# schemetics.net
KiCad netlist of a schematic drawn in EasyEDA
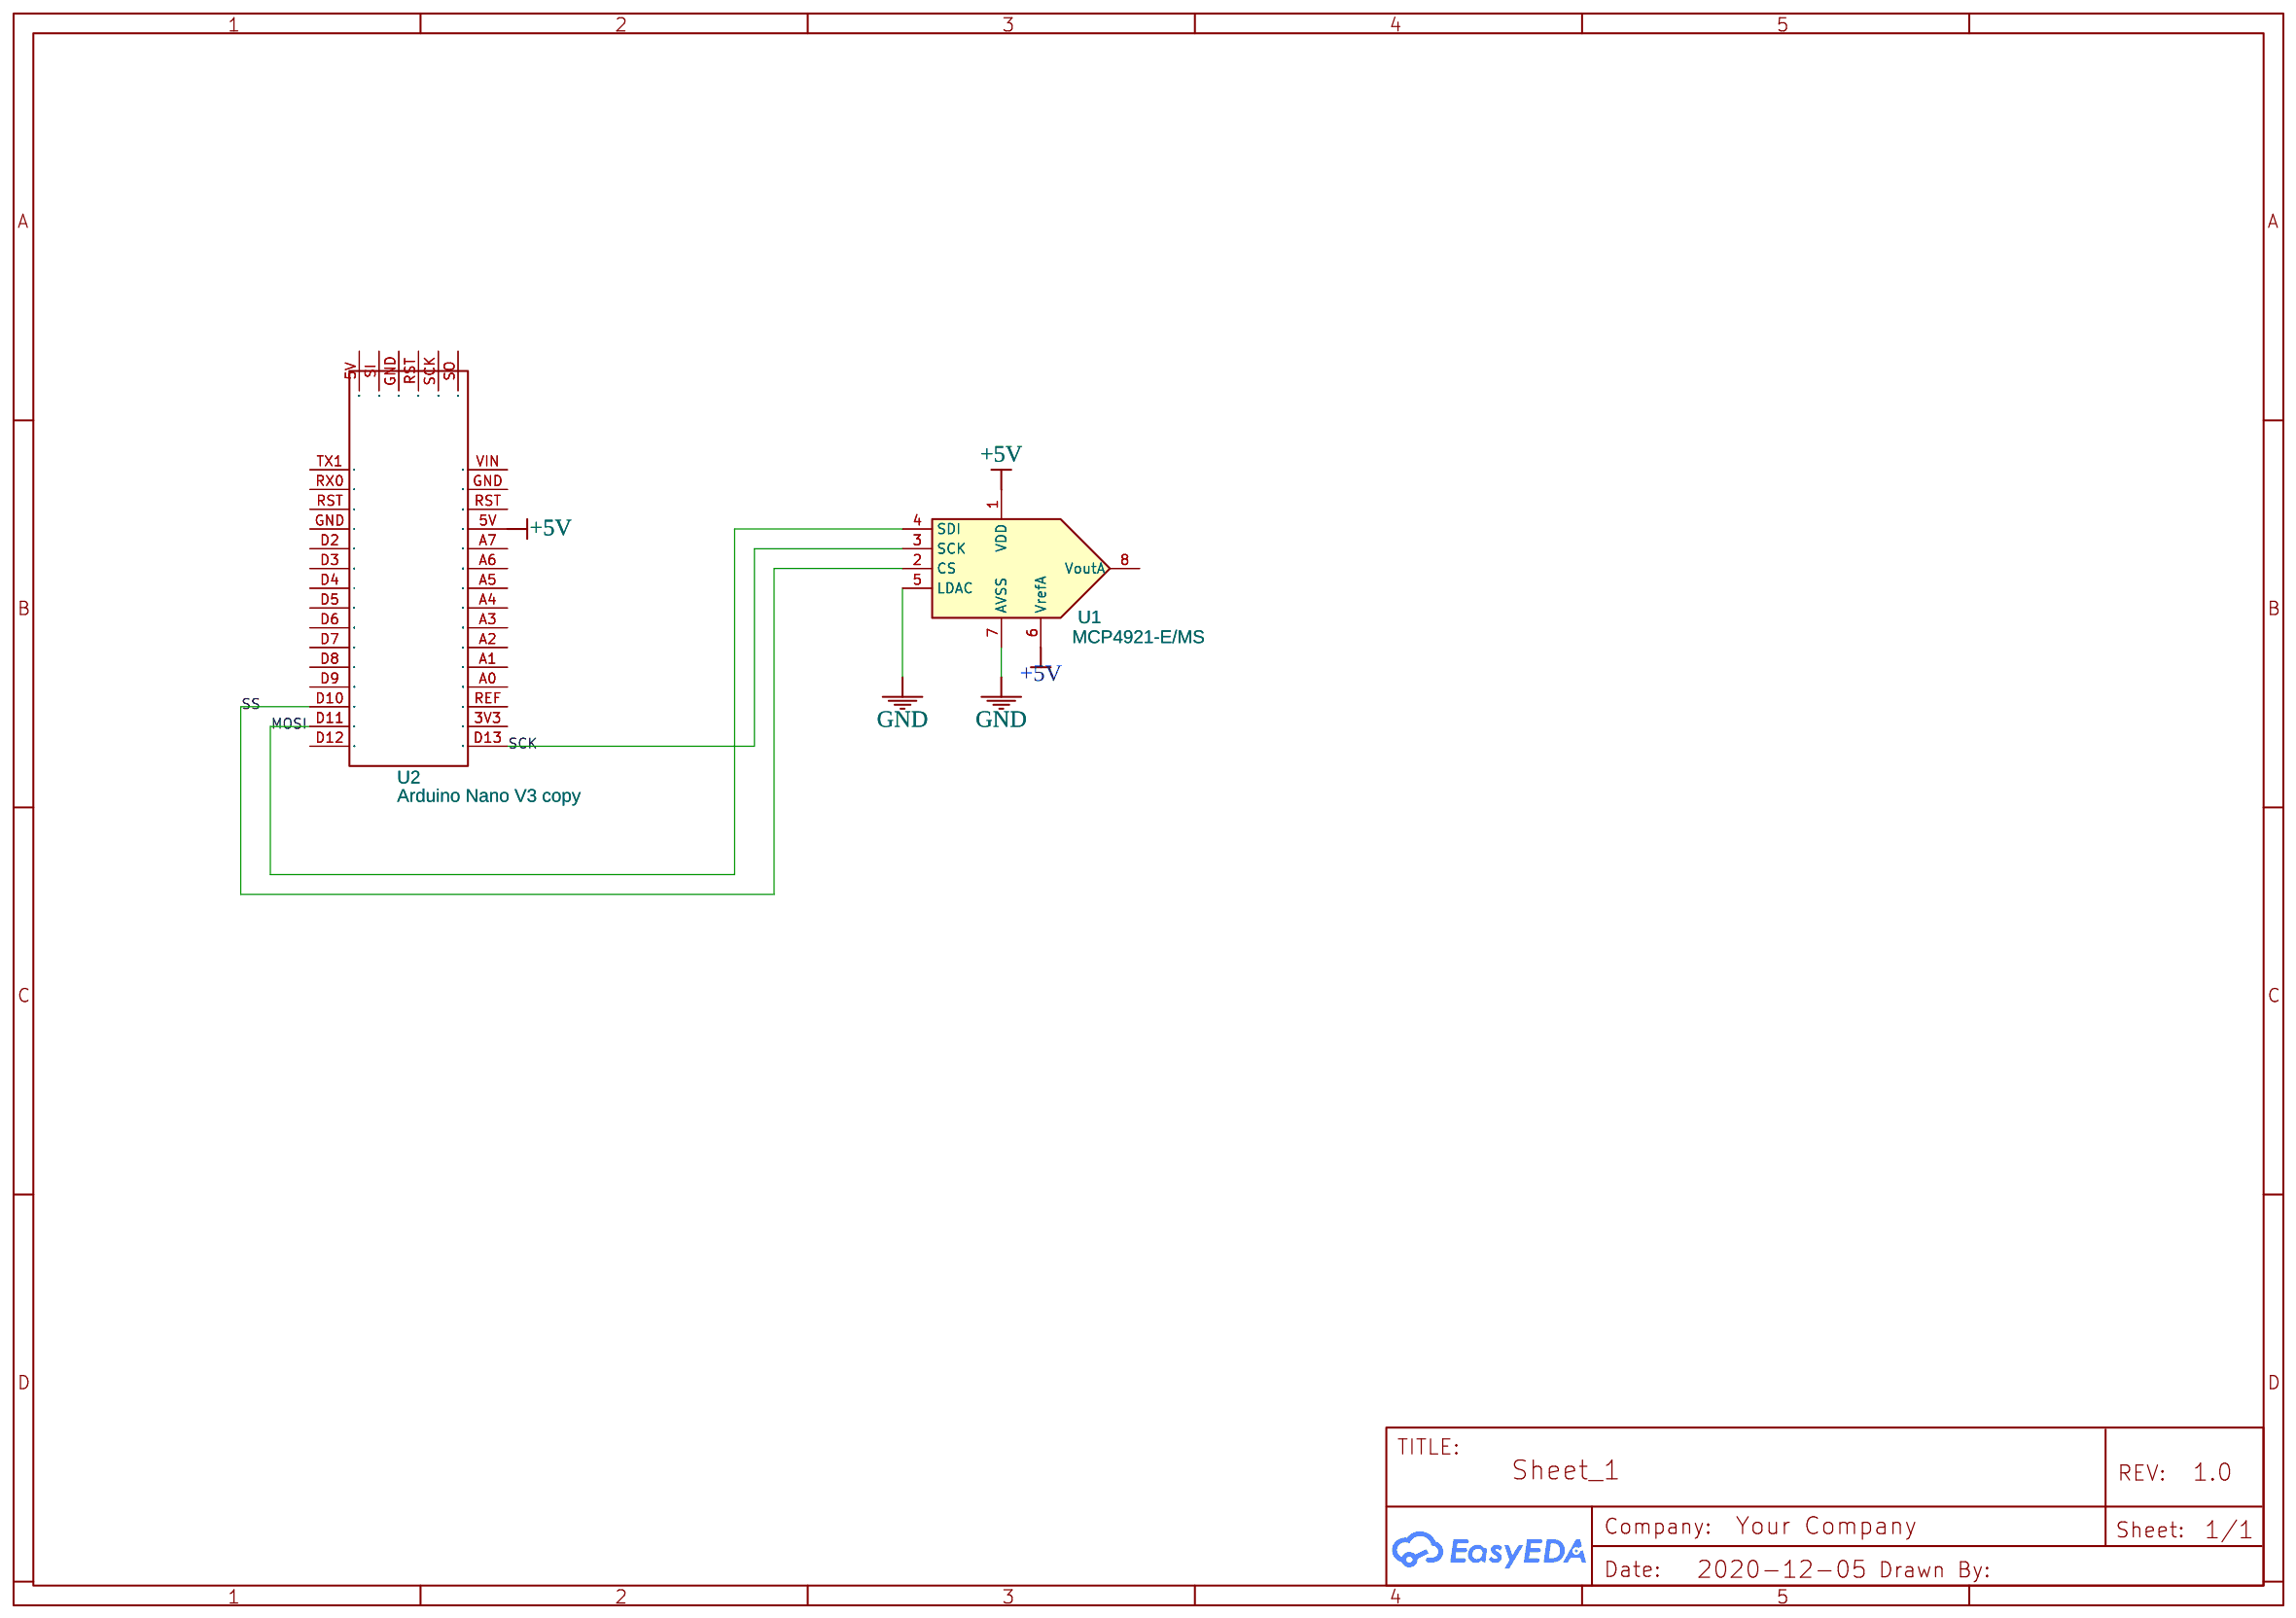
[diagram p0: schematic sheet]

(export (version "E")
  (design (tool "Eeschema 10.0.6"))
  (components
    (comp (ref "U1") (value "MCP4921-E/MS") (libsource (lib "") (part "MCP4921-E/MS")))
    (comp (ref "U2")
      (value "Arduino Nano V3 copy")
      (fields (field (name "BOM_Manufacturer Part") "Arduino Nano V3"))
      (libsource (lib "") (part "Arduino Nano V3 copy"))
    )
  )
  (nets
    (net (code "1") (name "+5V") (class "Default")
      (node (ref "U1") (pin "1") (pinfunction "VDD_1") (pintype "bidirectional"))
      (node (ref "U1") (pin "6") (pinfunction "VrefA_6") (pintype "unspecified"))
      (node (ref "U2") (pin "5V") (pinfunction "27_5V") (pintype "unspecified"))
    )
    (net (code "2") (name "/MOSI") (class "Default")
      (node (ref "U1") (pin "4") (pinfunction "SDI_4") (pintype "input"))
      (node (ref "U2") (pin "D11") (pinfunction "14_D11") (pintype "unspecified"))
    )
    (net (code "3") (name "/SCK") (class "Default")
      (node (ref "U1") (pin "3") (pinfunction "SCK_3") (pintype "input"))
      (node (ref "U2") (pin "D13") (pinfunction "16_D13") (pintype "unspecified"))
    )
    (net (code "4") (name "/SS") (class "Default")
      (node (ref "U1") (pin "2") (pinfunction "CS_2") (pintype "input"))
      (node (ref "U2") (pin "D10") (pinfunction "13_D10") (pintype "unspecified"))
    )
    (net (code "5") (name "GND") (class "Default")
      (node (ref "U1") (pin "5") (pinfunction "LDAC_5") (pintype "input"))
      (node (ref "U1") (pin "7") (pinfunction "AVSS_7") (pintype "bidirectional"))
    )
    (net (code "6") (name "unconnected-(U1-VoutA-Pad8)") (class "Default")
      (node (ref "U1") (pin "8") (pinfunction "VoutA_8") (pintype "unspecified"))
    )
    (net (code "7") (name "unconnected-(U2-1-PadTX1)") (class "Default")
      (node (ref "U2") (pin "TX1") (pinfunction "1_TX1") (pintype "unspecified"))
    )
    (net (code "8") (name "unconnected-(U2-2-PadRX0)") (class "Default")
      (node (ref "U2") (pin "RX0") (pinfunction "2_RX0") (pintype "unspecified"))
    )
    (net (code "9") (name "unconnected-(U2-3-PadRST)") (class "Default")
      (node (ref "U2") (pin "RST") (pinfunction "3_RST") (pintype "unspecified"))
    )
    (net (code "10") (name "unconnected-(U2-4-PadGND)") (class "Default")
      (node (ref "U2") (pin "GND") (pinfunction "4_GND") (pintype "unspecified"))
    )
    (net (code "11") (name "unconnected-(U2-5-PadD2)") (class "Default")
      (node (ref "U2") (pin "D2") (pinfunction "5_D2") (pintype "unspecified"))
    )
    (net (code "12") (name "unconnected-(U2-6-PadD3)") (class "Default")
      (node (ref "U2") (pin "D3") (pinfunction "6_D3") (pintype "unspecified"))
    )
    (net (code "13") (name "unconnected-(U2-7-PadD4)") (class "Default")
      (node (ref "U2") (pin "D4") (pinfunction "7_D4") (pintype "unspecified"))
    )
    (net (code "14") (name "unconnected-(U2-8-PadD5)") (class "Default")
      (node (ref "U2") (pin "D5") (pinfunction "8_D5") (pintype "unspecified"))
    )
    (net (code "15") (name "unconnected-(U2-9-PadD6)") (class "Default")
      (node (ref "U2") (pin "D6") (pinfunction "9_D6") (pintype "unspecified"))
    )
    (net (code "16") (name "unconnected-(U2-11-PadD8)") (class "Default")
      (node (ref "U2") (pin "D8") (pinfunction "11_D8") (pintype "unspecified"))
    )
    (net (code "17") (name "unconnected-(U2-12-PadD9)") (class "Default")
      (node (ref "U2") (pin "D9") (pinfunction "12_D9") (pintype "unspecified"))
    )
    (net (code "18") (name "unconnected-(U2-15-PadD12)") (class "Default")
      (node (ref "U2") (pin "D12") (pinfunction "15_D12") (pintype "unspecified"))
    )
    (net (code "19") (name "unconnected-(U2-17-Pad3V3)") (class "Default")
      (node (ref "U2") (pin "3V3") (pinfunction "17_3V3") (pintype "unspecified"))
    )
    (net (code "20") (name "unconnected-(U2-18-PadREF)") (class "Default")
      (node (ref "U2") (pin "REF") (pinfunction "18_REF") (pintype "unspecified"))
    )
    (net (code "21") (name "unconnected-(U2-19-PadA0)") (class "Default")
      (node (ref "U2") (pin "A0") (pinfunction "19_A0") (pintype "unspecified"))
    )
    (net (code "22") (name "unconnected-(U2-20-PadA1)") (class "Default")
      (node (ref "U2") (pin "A1") (pinfunction "20_A1") (pintype "unspecified"))
    )
    (net (code "23") (name "unconnected-(U2-21-PadA2)") (class "Default")
      (node (ref "U2") (pin "A2") (pinfunction "21_A2") (pintype "unspecified"))
    )
    (net (code "24") (name "unconnected-(U2-22-PadA3)") (class "Default")
      (node (ref "U2") (pin "A3") (pinfunction "22_A3") (pintype "unspecified"))
    )
    (net (code "25") (name "unconnected-(U2-23-PadA4)") (class "Default")
      (node (ref "U2") (pin "A4") (pinfunction "23_A4") (pintype "unspecified"))
    )
    (net (code "26") (name "unconnected-(U2-24-PadA5)") (class "Default")
      (node (ref "U2") (pin "A5") (pinfunction "24_A5") (pintype "unspecified"))
    )
    (net (code "27") (name "unconnected-(U2-25-PadA6)") (class "Default")
      (node (ref "U2") (pin "A6") (pinfunction "25_A6") (pintype "unspecified"))
    )
    (net (code "28") (name "unconnected-(U2-26-PadA7)") (class "Default")
      (node (ref "U2") (pin "A7") (pinfunction "26_A7") (pintype "unspecified"))
    )
    (net (code "29") (name "unconnected-(U2-28-PadRST)") (class "Default")
      (node (ref "U2") (pin "RST") (pinfunction "28_RST") (pintype "unspecified"))
    )
    (net (code "30") (name "unconnected-(U2-29-PadGND)") (class "Default")
      (node (ref "U2") (pin "GND") (pinfunction "29_GND") (pintype "unspecified"))
    )
    (net (code "31") (name "unconnected-(U2-30-PadVIN)") (class "Default")
      (node (ref "U2") (pin "VIN") (pinfunction "30_VIN") (pintype "unspecified"))
    )
    (net (code "32") (name "unconnected-(U2-31-PadSO)") (class "Default")
      (node (ref "U2") (pin "SO") (pinfunction "31_SO") (pintype "unspecified"))
    )
    (net (code "33") (name "unconnected-(U2-32-PadSCK)") (class "Default")
      (node (ref "U2") (pin "SCK") (pinfunction "32_SCK") (pintype "unspecified"))
    )
    (net (code "34") (name "unconnected-(U2-33-PadRST)") (class "Default")
      (node (ref "U2") (pin "RST") (pinfunction "33_RST") (pintype "unspecified"))
    )
    (net (code "35") (name "unconnected-(U2-34-PadGND)") (class "Default")
      (node (ref "U2") (pin "GND") (pinfunction "34_GND") (pintype "unspecified"))
    )
    (net (code "36") (name "unconnected-(U2-35-PadSI)") (class "Default")
      (node (ref "U2") (pin "SI") (pinfunction "35_SI") (pintype "unspecified"))
    )
    (net (code "37") (name "unconnected-(U2-36-Pad5V)") (class "Default")
      (node (ref "U2") (pin "5V") (pinfunction "36_5V") (pintype "unspecified"))
    )
    (net (code "38") (name "unconnected-(U2-PadD7)") (class "Default")
      (node (ref "U2") (pin "D7") (pinfunction "D7_D7") (pintype "unspecified"))
    )
  )
)
